# Pot4_2_MCP3008.net
KiCad netlist of a schematic drawn in EAGLE
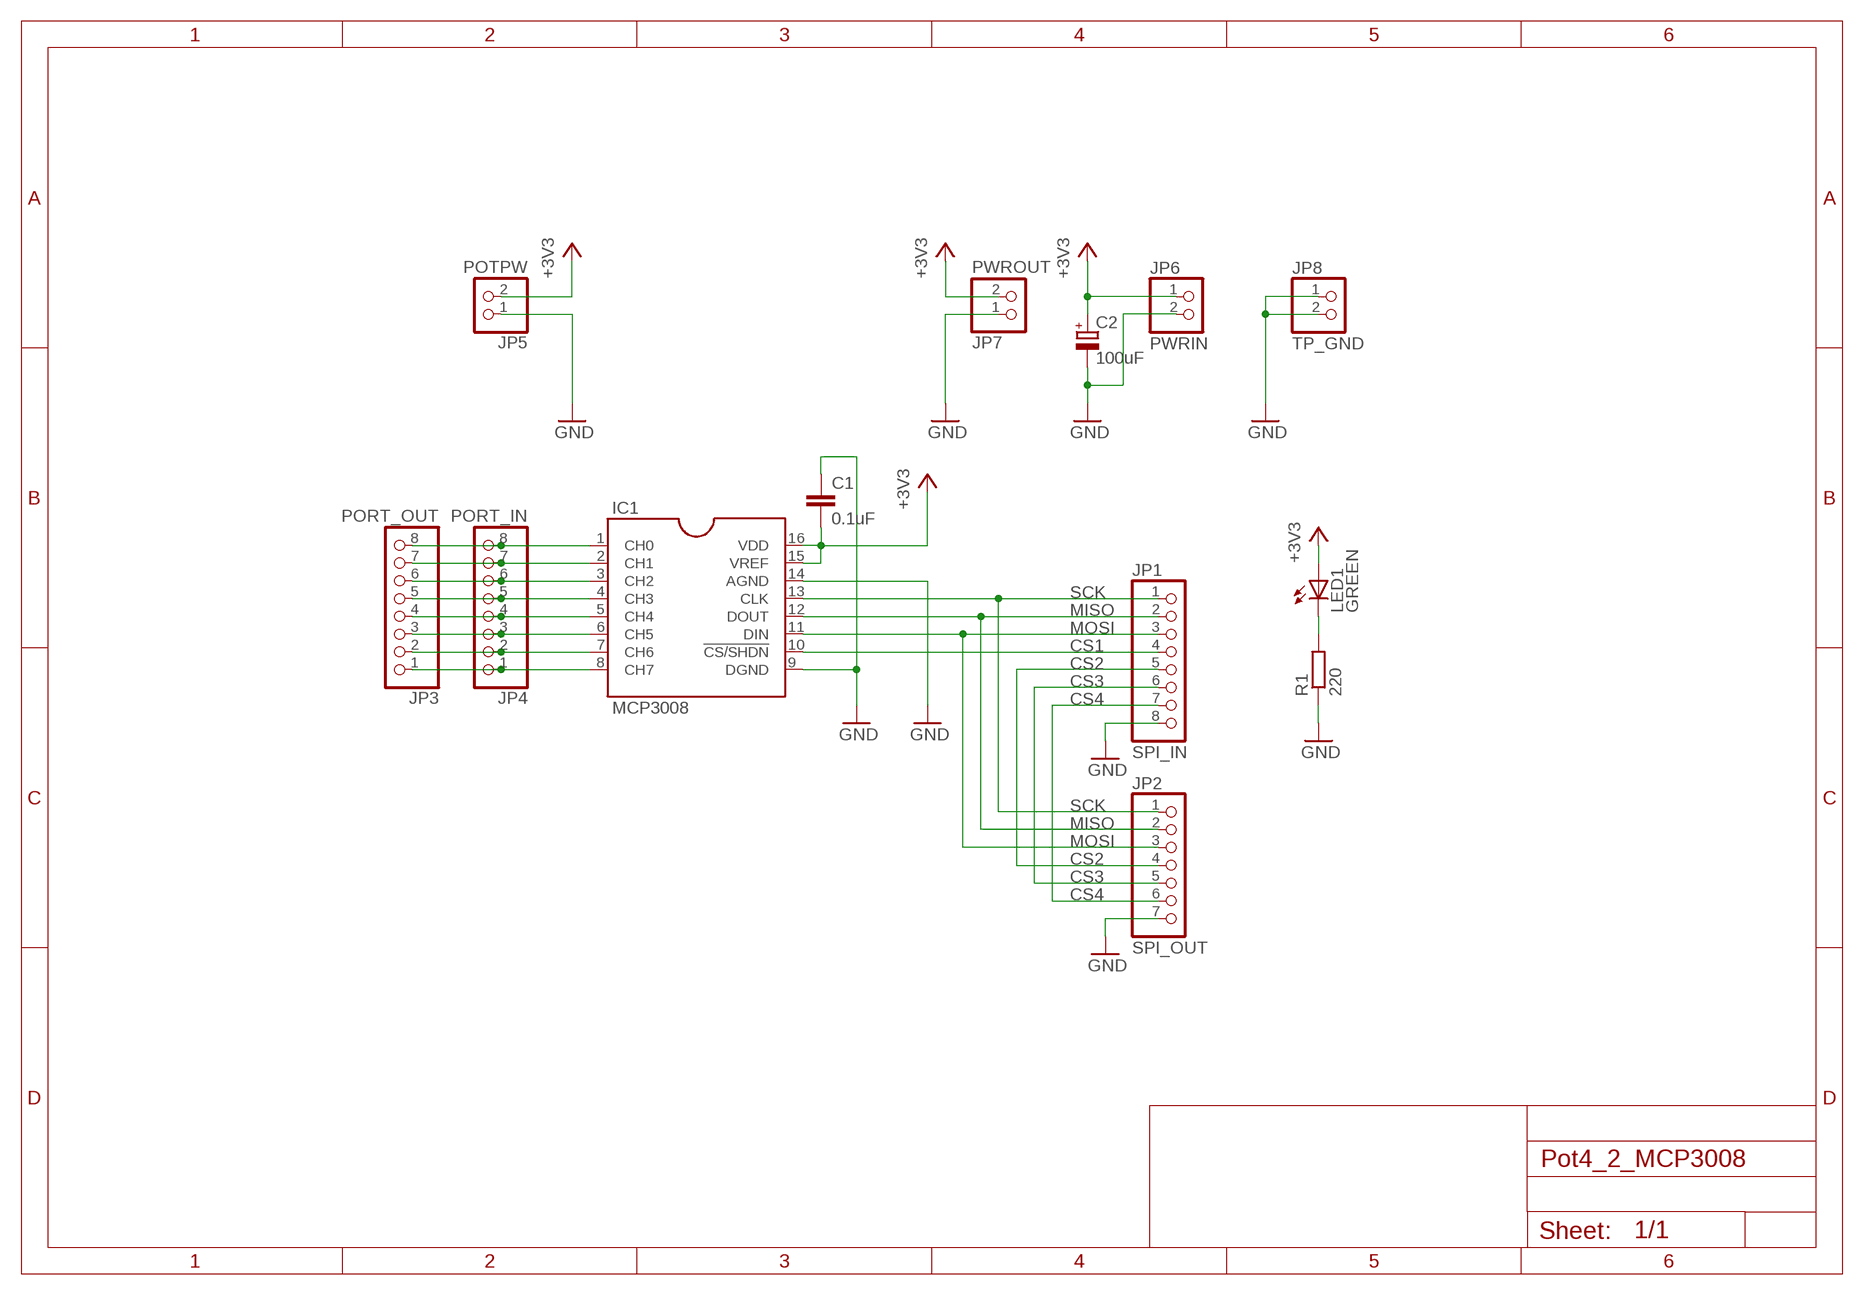
[diagram p0: schematic, sheet 1]

(export (version "E")
  (design (tool "Eeschema 10.0.6"))
  (components
    (comp (ref "C1")
      (value "0.1uF")
      (footprint "eagle-import:C025-024X044")
      (libsource (lib "eagle-import") (part "C-EU025-024X044"))
    )
    (comp (ref "C2")
      (value "100uF")
      (footprint "eagle-import:E2,5-7")
      (libsource (lib "eagle-import") (part "CPOL-EUE2.5-7"))
    )
    (comp (ref "IC1")
      (value "MCP3008")
      (footprint "eagle-import:MCP3008")
      (libsource (lib "eagle-import") (part "MCP3008"))
    )
    (comp (ref "JP1")
      (value "SPI_IN")
      (footprint "eagle-import:1X08_90")
      (libsource (lib "eagle-import") (part "PINHD-1X8/90"))
    )
    (comp (ref "JP2")
      (value "SPI_OUT")
      (footprint "eagle-import:1X07_90")
      (libsource (lib "eagle-import") (part "PINHD-1X7/90"))
    )
    (comp (ref "JP3")
      (value "PORT_OUT")
      (footprint "eagle-import:1X08")
      (libsource (lib "eagle-import") (part "PINHD-1X8"))
    )
    (comp (ref "JP4")
      (value "PORT_IN")
      (footprint "eagle-import:1X08_90")
      (libsource (lib "eagle-import") (part "PINHD-1X8/90"))
    )
    (comp (ref "JP5")
      (value "POTPW")
      (footprint "eagle-import:1X02_90")
      (libsource (lib "eagle-import") (part "PINHD-1X2/90"))
    )
    (comp (ref "JP6")
      (value "PWRIN")
      (footprint "eagle-import:1X02_90")
      (libsource (lib "eagle-import") (part "PINHD-1X2/90"))
    )
    (comp (ref "JP7")
      (value "PWROUT")
      (footprint "eagle-import:1X02_90")
      (libsource (lib "eagle-import") (part "PINHD-1X2/90"))
    )
    (comp (ref "JP8")
      (value "TP_GND")
      (footprint "eagle-import:1X02")
      (libsource (lib "eagle-import") (part "PINHD-1X2"))
    )
    (comp (ref "LED1")
      (value "GREEN")
      (footprint "eagle-import:LED3MM")
      (libsource (lib "eagle-import") (part "LED3MM"))
    )
    (comp (ref "R1")
      (value "220")
      (footprint "eagle-import:0207_7")
      (libsource (lib "eagle-import") (part "R-EU_0207/7"))
    )
  )
  (nets
    (net (code "1") (name "+3V3") (class "Default")
      (node (ref "C1") (pin "2") (pinfunction "2_2") (pintype "passive"))
      (node (ref "C2") (pin "+") (pinfunction "+_+") (pintype "passive"))
      (node (ref "IC1") (pin "15") (pinfunction "VREF_15") (pintype "passive"))
      (node (ref "IC1") (pin "16") (pinfunction "VDD_16") (pintype "passive"))
      (node (ref "JP5") (pin "2") (pinfunction "2_2") (pintype "passive"))
      (node (ref "JP6") (pin "1") (pinfunction "1_1") (pintype "passive"))
      (node (ref "JP7") (pin "2") (pinfunction "2_2") (pintype "passive"))
      (node (ref "LED1") (pin "A") (pinfunction "A_A") (pintype "passive"))
    )
    (net (code "2") (name "/CS1") (class "Default")
      (node (ref "IC1") (pin "10") (pinfunction "~{CS/SHDN}_10") (pintype "passive"))
      (node (ref "JP1") (pin "4") (pinfunction "4_4") (pintype "passive"))
    )
    (net (code "3") (name "/CS2") (class "Default")
      (node (ref "JP1") (pin "5") (pinfunction "5_5") (pintype "passive"))
      (node (ref "JP2") (pin "4") (pinfunction "4_4") (pintype "passive"))
    )
    (net (code "4") (name "/CS3") (class "Default")
      (node (ref "JP1") (pin "6") (pinfunction "6_6") (pintype "passive"))
      (node (ref "JP2") (pin "5") (pinfunction "5_5") (pintype "passive"))
    )
    (net (code "5") (name "/CS4") (class "Default")
      (node (ref "JP1") (pin "7") (pinfunction "7_7") (pintype "passive"))
      (node (ref "JP2") (pin "6") (pinfunction "6_6") (pintype "passive"))
    )
    (net (code "6") (name "/MISO") (class "Default")
      (node (ref "IC1") (pin "12") (pinfunction "DOUT_12") (pintype "passive"))
      (node (ref "JP1") (pin "2") (pinfunction "2_2") (pintype "passive"))
      (node (ref "JP2") (pin "2") (pinfunction "2_2") (pintype "passive"))
    )
    (net (code "7") (name "/MOSI") (class "Default")
      (node (ref "IC1") (pin "11") (pinfunction "DIN_11") (pintype "passive"))
      (node (ref "JP1") (pin "3") (pinfunction "3_3") (pintype "passive"))
      (node (ref "JP2") (pin "3") (pinfunction "3_3") (pintype "passive"))
    )
    (net (code "8") (name "/SCK") (class "Default")
      (node (ref "IC1") (pin "13") (pinfunction "CLK_13") (pintype "passive"))
      (node (ref "JP1") (pin "1") (pinfunction "1_1") (pintype "passive"))
      (node (ref "JP2") (pin "1") (pinfunction "1_1") (pintype "passive"))
    )
    (net (code "9") (name "GND") (class "Default")
      (node (ref "C1") (pin "1") (pinfunction "1_1") (pintype "passive"))
      (node (ref "C2") (pin "-") (pinfunction "-_-") (pintype "passive"))
      (node (ref "IC1") (pin "14") (pinfunction "AGND_14") (pintype "passive"))
      (node (ref "IC1") (pin "9") (pinfunction "DGND_9") (pintype "passive"))
      (node (ref "JP1") (pin "8") (pinfunction "8_8") (pintype "passive"))
      (node (ref "JP2") (pin "7") (pinfunction "7_7") (pintype "passive"))
      (node (ref "JP5") (pin "1") (pinfunction "1_1") (pintype "passive"))
      (node (ref "JP6") (pin "2") (pinfunction "2_2") (pintype "passive"))
      (node (ref "JP7") (pin "1") (pinfunction "1_1") (pintype "passive"))
      (node (ref "JP8") (pin "1") (pinfunction "1_1") (pintype "passive"))
      (node (ref "JP8") (pin "2") (pinfunction "2_2") (pintype "passive"))
      (node (ref "R1") (pin "1") (pinfunction "1_1") (pintype "passive"))
    )
    (net (code "10") (name "Net-(IC1-CH0)") (class "Default")
      (node (ref "IC1") (pin "1") (pinfunction "CH0_1") (pintype "passive"))
      (node (ref "JP3") (pin "8") (pinfunction "8_8") (pintype "passive"))
      (node (ref "JP4") (pin "8") (pinfunction "8_8") (pintype "passive"))
    )
    (net (code "11") (name "Net-(IC1-CH1)") (class "Default")
      (node (ref "IC1") (pin "2") (pinfunction "CH1_2") (pintype "passive"))
      (node (ref "JP3") (pin "7") (pinfunction "7_7") (pintype "passive"))
      (node (ref "JP4") (pin "7") (pinfunction "7_7") (pintype "passive"))
    )
    (net (code "12") (name "Net-(IC1-CH2)") (class "Default")
      (node (ref "IC1") (pin "3") (pinfunction "CH2_3") (pintype "passive"))
      (node (ref "JP3") (pin "6") (pinfunction "6_6") (pintype "passive"))
      (node (ref "JP4") (pin "6") (pinfunction "6_6") (pintype "passive"))
    )
    (net (code "13") (name "Net-(IC1-CH3)") (class "Default")
      (node (ref "IC1") (pin "4") (pinfunction "CH3_4") (pintype "passive"))
      (node (ref "JP3") (pin "5") (pinfunction "5_5") (pintype "passive"))
      (node (ref "JP4") (pin "5") (pinfunction "5_5") (pintype "passive"))
    )
    (net (code "14") (name "Net-(IC1-CH4)") (class "Default")
      (node (ref "IC1") (pin "5") (pinfunction "CH4_5") (pintype "passive"))
      (node (ref "JP3") (pin "4") (pinfunction "4_4") (pintype "passive"))
      (node (ref "JP4") (pin "4") (pinfunction "4_4") (pintype "passive"))
    )
    (net (code "15") (name "Net-(IC1-CH5)") (class "Default")
      (node (ref "IC1") (pin "6") (pinfunction "CH5_6") (pintype "passive"))
      (node (ref "JP3") (pin "3") (pinfunction "3_3") (pintype "passive"))
      (node (ref "JP4") (pin "3") (pinfunction "3_3") (pintype "passive"))
    )
    (net (code "16") (name "Net-(IC1-CH6)") (class "Default")
      (node (ref "IC1") (pin "7") (pinfunction "CH6_7") (pintype "passive"))
      (node (ref "JP3") (pin "2") (pinfunction "2_2") (pintype "passive"))
      (node (ref "JP4") (pin "2") (pinfunction "2_2") (pintype "passive"))
    )
    (net (code "17") (name "Net-(IC1-CH7)") (class "Default")
      (node (ref "IC1") (pin "8") (pinfunction "CH7_8") (pintype "passive"))
      (node (ref "JP3") (pin "1") (pinfunction "1_1") (pintype "passive"))
      (node (ref "JP4") (pin "1") (pinfunction "1_1") (pintype "passive"))
    )
    (net (code "18") (name "Net-(LED1-C)") (class "Default")
      (node (ref "LED1") (pin "K") (pinfunction "C_K") (pintype "passive"))
      (node (ref "R1") (pin "2") (pinfunction "2_2") (pintype "passive"))
    )
  )
)
